# CONNECTORS_SELECTORS.net
KiCad netlist of a schematic drawn in Altium Designer
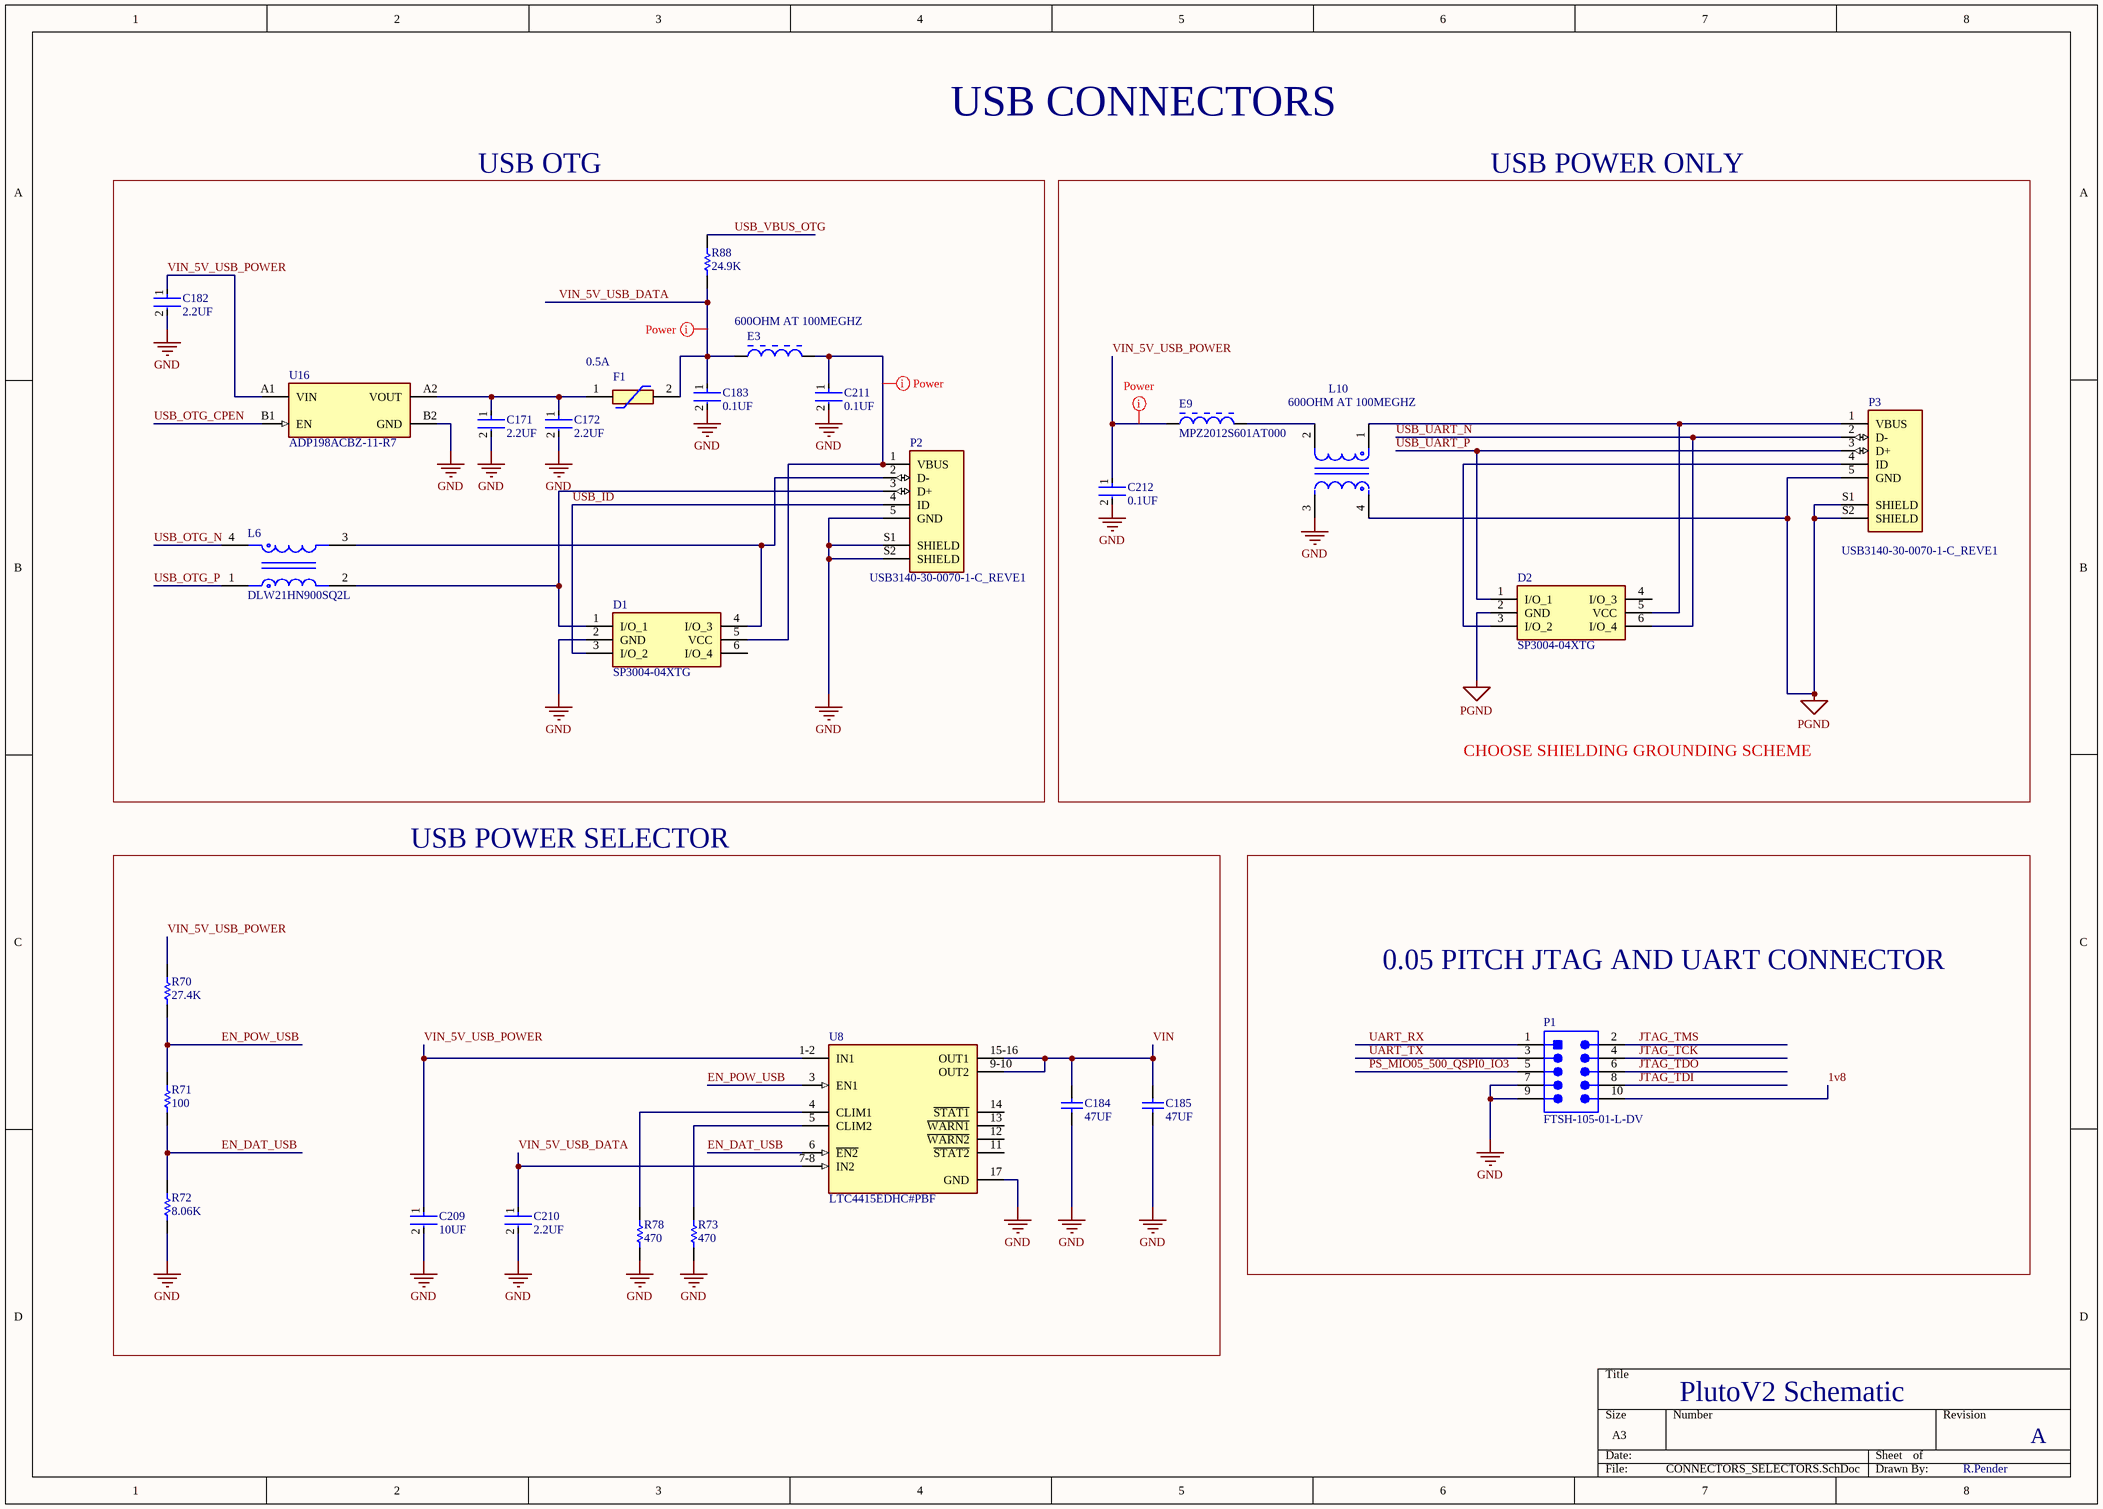
[diagram p0: CONNECTORS_SELECTORS.SchDoc]

(export (version "E")
  (design (tool "Eeschema 10.0.6"))
  (components
    (comp (ref "C171")
      (value "2.2UF")
      (footprint "FP-GRM188-0_2-IPC_C")
      (description "Chip Multilayer Ceramic Capacitors for General Purpose, 0603, 2.2uF, X5R, 15%, 10%, 50V")
      (fields (field (name "TOLERANCE") "10%"))
      (libsource (lib "Altium Content Vault") (part "11868f565c42a9108669ba33697ecf6"))
    )
    (comp (ref "C172")
      (value "2.2UF")
      (footprint "FP-GRM188-0_2-IPC_C")
      (description "Chip Multilayer Ceramic Capacitors for General Purpose, 0603, 2.2uF, X5R, 15%, 10%, 50V")
      (fields (field (name "TOLERANCE") "10%"))
      (libsource (lib "Altium Content Vault") (part "11868f565c42a9108669ba33697ecf6"))
    )
    (comp (ref "C182")
      (value "2.2UF")
      (footprint "FP-GRM188-0_2-IPC_C")
      (description "Chip Multilayer Ceramic Capacitors for General Purpose, 0603, 2.2uF, X5R, 15%, 10%, 50V")
      (fields (field (name "TOLERANCE") "10%"))
      (libsource (lib "Altium Content Vault") (part "11868f565c42a9108669ba33697ecf6"))
    )
    (comp (ref "C183")
      (value "0.1UF")
      (footprint "FP-CL10-IPC_A")
      (description "Cap Ceramic 100nF 100V X7R ±10% Pad SMD 0603 +125°C T/R")
      (fields (field (name "TOLERANCE") "10%"))
      (libsource (lib "Altium Content Vault") (part "b4654b650e69147ec39a6b967a45e02"))
    )
    (comp (ref "C184")
      (value "47UF")
      (footprint "TAYO-JMK212BBJ476MG-T_L")
      (fields
        (field (name "MANUFACTURER") "Taiyo Yuden")
        (field (name "TOLERANCE") "±20%")
        (field (name "PCN PART NUMBER") "X5R,X7RDielectrics23/Jan/2008")
      )
      (libsource (lib "Altium Content Vault") (part "CAP-NP-2"))
    )
    (comp (ref "C185")
      (value "47UF")
      (footprint "TAYO-JMK212BBJ476MG-T_L")
      (fields
        (field (name "MANUFACTURER") "Taiyo Yuden")
        (field (name "TOLERANCE") "±20%")
        (field (name "PCN PART NUMBER") "X5R,X7RDielectrics23/Jan/2008")
      )
      (libsource (lib "Altium Content Vault") (part "CAP-NP-2"))
    )
    (comp (ref "C209")
      (value "10UF")
      (footprint "FP-GRM188-0_15-MFG")
      (description "Chip Multilayer Ceramic Capacitors for General Purpose, 0603, 10uF, X5R, 15%, 20%, 10V")
      (fields (field (name "TOLERANCE") "20%"))
      (libsource (lib "Altium Content Vault") (part "02cd4be3c70576c341d710602a673aa"))
    )
    (comp (ref "C210")
      (value "2.2UF")
      (footprint "FP-GRM188-0_2-IPC_C")
      (description "Chip Multilayer Ceramic Capacitors for General Purpose, 0603, 2.2uF, X5R, 15%, 10%, 50V")
      (fields (field (name "TOLERANCE") "10%"))
      (libsource (lib "Altium Content Vault") (part "11868f565c42a9108669ba33697ecf6"))
    )
    (comp (ref "C211")
      (value "0.1UF")
      (footprint "FP-CL10-IPC_A")
      (description "Cap Ceramic 100nF 100V X7R ±10% Pad SMD 0603 +125°C T/R")
      (fields (field (name "TOLERANCE") "10%"))
      (libsource (lib "Altium Content Vault") (part "b4654b650e69147ec39a6b967a45e02"))
    )
    (comp (ref "C212")
      (value "0.1UF")
      (footprint "FP-CL10-IPC_A")
      (description "Cap Ceramic 100nF 100V X7R ±10% Pad SMD 0603 +125°C T/R")
      (fields (field (name "TOLERANCE") "10%"))
      (libsource (lib "Altium Content Vault") (part "b4654b650e69147ec39a6b967a45e02"))
    )
    (comp (ref "D1")
      (value "SP3004-04XTG")
      (footprint "SamacSys:SOTFL50P160X60-6N")
      (description "TVS Diode (Uni-directional)")
      (libsource (lib "SamacSys") (part "SP3004-04XTG"))
    )
    (comp (ref "D2")
      (value "SP3004-04XTG")
      (footprint "SamacSys:SOTFL50P160X60-6N")
      (description "TVS Diode (Uni-directional)")
      (libsource (lib "SamacSys") (part "SP3004-04XTG"))
    )
    (comp (ref "E3")
      (value "600OHM AT 100MEGHZ")
      (footprint "TDK-MPZ2012_V")
      (description "Chip Bead, 0.1 Ohm, 2 A, -55 to 125 degC, 2-Pin SMD (0805), RoHS, Tape and Reel")
      (fields (field (name "PCN PART NUMBER") "MMZ,MPSSeriesOct/2014") (field (name "MANUFACTURER") "TDK"))
      (libsource (lib "Altium Content Vault") (part "BEAD-2"))
    )
    (comp (ref "E9")
      (value "MPZ2012S601AT000")
      (footprint "TDK-MPZ2012_V")
      (description "Chip Bead, 0.1 Ohm, 2 A, -55 to 125 degC, 2-Pin SMD (0805), RoHS, Tape and Reel")
      (fields (field (name "PCN PART NUMBER") "MMZ,MPSSeriesOct/2014") (field (name "MANUFACTURER") "TDK"))
      (libsource (lib "Altium Content Vault") (part "BEAD-2"))
    )
    (comp (ref "F1")
      (value "0.5A")
      (footprint "SamacSys:0402L010SLKR")
      (description "Resettable Fuse")
      (fields (field (name "MANUFACTURER_PART_NUMBER") "0402L050SLKR"))
      (libsource (lib "SamacSys") (part "0402L050SLKR"))
    )
    (comp (ref "L6")
      (value "DLW21HN900SQ2L")
      (footprint "FP-DLW21HN-MFG")
      (description "CMC 330MA 2LN 90 OHM SMD")
      (fields (field (name "TOLERANCE") "25%"))
      (libsource (lib "Altium Content Vault") (part "0a69a9865a8fa8fb197e9315ef85d0a"))
    )
    (comp (ref "L10")
      (value "600OHM AT 100MEGHZ")
      (footprint "FP-DLW5BS-MFG")
      (description "Common Mode Choke, 2020, 800Ω @ 100MHz, 0.056Ω, 40%, 2A")
      (fields (field (name "TOLERANCE") "40%"))
      (libsource (lib "Altium Content Vault") (part "7e18bf8fdb9f2485ca2bcdf9073d69f"))
    )
    (comp (ref "P1")
      (value "FTSH-105-01-L-DV")
      (footprint "SMTC-FTSH-105-01-L-DV_V")
      (description "Male Header, Pitch 1.27 mm, 2 x 5 Position, Height 5.96 mm, -55 to 125 degC, RoHS, Bulk")
      (fields (field (name "MANUFACTURER") "Samtec"))
      (libsource (lib "Altium Content Vault") (part "CN-2P-M-R10"))
    )
    (comp (ref "P2")
      (value "USB3140-30-0070-1-C_REVE1")
      (footprint "GCT_USB3140-30-0070-1-C_REVE1")
      (fields (field (name "MF") "Global Connector Technology") (field (name "MP") "USB3140-30-0070-1-C"))
      (libsource (lib "USB3140-30-0070-1-C_REVE1") (part "USB3140-30-0070-1-C_REVE1"))
    )
    (comp (ref "P3")
      (value "USB3140-30-0070-1-C_REVE1")
      (footprint "GCT_USB3140-30-0070-1-C_REVE1")
      (fields (field (name "MF") "Global Connector Technology") (field (name "MP") "USB3140-30-0070-1-C"))
      (libsource (lib "USB3140-30-0070-1-C_REVE1") (part "USB3140-30-0070-1-C_REVE1"))
    )
    (comp (ref "R70")
      (value "27.4K")
      (footprint "2-0402")
      (fields (field (name "PUBLISHER") "Altium Limited"))
      (libsource (lib "Panasonic Resistor") (part "ERJ2RK"))
    )
    (comp (ref "R71")
      (value "100")
      (footprint "2-0402")
      (fields (field (name "PUBLISHER") "Altium Limited"))
      (libsource (lib "Panasonic Resistor") (part "ERJ2RK"))
    )
    (comp (ref "R72")
      (value "8.06K")
      (footprint "2-0402")
      (fields (field (name "PUBLISHER") "Altium Limited"))
      (libsource (lib "Panasonic Resistor") (part "ERJ2RK"))
    )
    (comp (ref "R73")
      (value "470")
      (footprint "RESC1005X40X25ML05T10")
      (fields (field (name "PART NUMBER") "RC0402FR-07470RL") (field (name "MANUFACTURER") "Yageo / Phycomp"))
      (libsource (lib "Altium Content Vault") (part "RES"))
    )
    (comp (ref "R78")
      (value "470")
      (footprint "RESC1005X40X25ML05T10")
      (fields (field (name "PART NUMBER") "RC0402FR-07470RL") (field (name "MANUFACTURER") "Yageo / Phycomp"))
      (libsource (lib "Altium Content Vault") (part "RES"))
    )
    (comp (ref "R88")
      (value "24.9K")
      (footprint "2-0402")
      (fields (field (name "PUBLISHER") "Altium Limited"))
      (libsource (lib "Panasonic Resistor") (part "ERJ2RK"))
    )
    (comp (ref "U8")
      (value "LTC4415EDHC#PBF")
      (footprint "FP-DHC-16-05-08-1872-MFG")
      (description "IC OR CTRLR SRC SELECT 16DFN")
      (libsource (lib "Altium Content Vault") (part "3ca062e251a206593296efba02ab3fb"))
    )
    (comp (ref "U16")
      (value "ADP198ACBZ-11-R7")
      (footprint "FP-CB-4-4-MFG")
      (description "IC PWR SWITCH P-CHAN 1:1 4WLCSP")
      (libsource (lib "Altium Content Vault") (part "e79baadf0d63db38dbad7ddd3c26481"))
    )
  )
  (nets
    (net (code "1") (name "/1v8") (class "Default")
      (node (ref "P1") (pin "10") (pinfunction "10_10") (pintype "passive"))
    )
    (net (code "2") (name "/EN_DAT_USB") (class "Default")
      (node (ref "R71") (pin "2") (pinfunction "2_2") (pintype "passive"))
      (node (ref "R72") (pin "1") (pinfunction "1_1") (pintype "passive"))
      (node (ref "U8") (pin "6") (pinfunction "~{EN2}_6") (pintype "input"))
    )
    (net (code "3") (name "/EN_POW_USB") (class "Default")
      (node (ref "R70") (pin "2") (pinfunction "2_2") (pintype "passive"))
      (node (ref "R71") (pin "1") (pinfunction "1_1") (pintype "passive"))
      (node (ref "U8") (pin "3") (pinfunction "EN1_3") (pintype "input"))
    )
    (net (code "4") (name "/JTAG_TCK") (class "Default")
      (node (ref "P1") (pin "4") (pinfunction "4_4") (pintype "passive"))
    )
    (net (code "5") (name "/JTAG_TDI") (class "Default")
      (node (ref "P1") (pin "8") (pinfunction "8_8") (pintype "passive"))
    )
    (net (code "6") (name "/JTAG_TDO") (class "Default")
      (node (ref "P1") (pin "6") (pinfunction "6_6") (pintype "passive"))
    )
    (net (code "7") (name "/JTAG_TMS") (class "Default")
      (node (ref "P1") (pin "2") (pinfunction "2_2") (pintype "passive"))
    )
    (net (code "8") (name "/PS_MIO05_500_QSPI0_IO3") (class "Default")
      (node (ref "P1") (pin "5") (pinfunction "5_5") (pintype "passive"))
    )
    (net (code "9") (name "/UART_RX") (class "Default")
      (node (ref "P1") (pin "1") (pinfunction "1_1") (pintype "passive"))
    )
    (net (code "10") (name "/UART_TX") (class "Default")
      (node (ref "P1") (pin "3") (pinfunction "3_3") (pintype "passive"))
    )
    (net (code "11") (name "/USB_ID") (class "Default")
      (node (ref "D1") (pin "3") (pinfunction "I/O_2_3") (pintype "passive"))
      (node (ref "P2") (pin "4") (pinfunction "ID_4") (pintype "passive"))
    )
    (net (code "12") (name "/USB_OTG_CPEN") (class "Default")
      (node (ref "U16") (pin "B1") (pinfunction "EN_B1") (pintype "input"))
    )
    (net (code "13") (name "/USB_OTG_N") (class "Default")
      (node (ref "L6") (pin "4") (pinfunction "4_4") (pintype "passive"))
    )
    (net (code "14") (name "/USB_OTG_P") (class "Default")
      (node (ref "L6") (pin "1") (pinfunction "1_1") (pintype "passive"))
    )
    (net (code "15") (name "/USB_UART_N") (class "Default")
      (node (ref "D2") (pin "6") (pinfunction "I/O_4_6") (pintype "passive"))
      (node (ref "P3") (pin "2") (pinfunction "D-_2") (pintype "bidirectional"))
    )
    (net (code "16") (name "/USB_UART_P") (class "Default")
      (node (ref "D2") (pin "1") (pinfunction "I/O_1_1") (pintype "passive"))
      (node (ref "P3") (pin "3") (pinfunction "D+_3") (pintype "bidirectional"))
    )
    (net (code "17") (name "/USB_VBUS_OTG") (class "Default")
      (node (ref "R88") (pin "2") (pinfunction "2_2") (pintype "passive"))
    )
    (net (code "18") (name "/VIN") (class "Default")
      (node (ref "C184") (pin "1") (pinfunction "1_1") (pintype "passive"))
      (node (ref "C185") (pin "1") (pinfunction "1_1") (pintype "passive"))
      (node (ref "U8") (pin "15-16") (pinfunction "OUT1_15-16") (pintype "passive"))
      (node (ref "U8") (pin "9-10") (pinfunction "OUT2_9-10") (pintype "passive"))
    )
    (net (code "19") (name "/VIN_5V_USB_DATA") (class "Default")
      (node (ref "C183") (pin "1") (pinfunction "1_1") (pintype "passive"))
      (node (ref "C210") (pin "1") (pinfunction "1_1") (pintype "passive"))
      (node (ref "E3") (pin "1") (pinfunction "1_1") (pintype "passive"))
      (node (ref "F1") (pin "2") (pinfunction "2_2") (pintype "passive"))
      (node (ref "R88") (pin "1") (pinfunction "1_1") (pintype "passive"))
      (node (ref "U8") (pin "7-8") (pinfunction "IN2_7-8") (pintype "input"))
    )
    (net (code "20") (name "/VIN_5V_USB_POWER") (class "Default")
      (node (ref "C182") (pin "1") (pinfunction "1_1") (pintype "passive"))
      (node (ref "C209") (pin "1") (pinfunction "1_1") (pintype "passive"))
      (node (ref "C212") (pin "1") (pinfunction "1_1") (pintype "passive"))
      (node (ref "E9") (pin "1") (pinfunction "1_1") (pintype "passive"))
      (node (ref "R70") (pin "1") (pinfunction "1_1") (pintype "passive"))
      (node (ref "U16") (pin "A1") (pinfunction "VIN_A1") (pintype "power_in"))
      (node (ref "U8") (pin "1-2") (pinfunction "IN1_1-2") (pintype "power_in"))
    )
    (net (code "21") (name "GND") (class "Default")
      (node (ref "C171") (pin "2") (pinfunction "2_2") (pintype "passive"))
      (node (ref "C172") (pin "2") (pinfunction "2_2") (pintype "passive"))
      (node (ref "C182") (pin "2") (pinfunction "2_2") (pintype "passive"))
      (node (ref "C183") (pin "2") (pinfunction "2_2") (pintype "passive"))
      (node (ref "C184") (pin "2") (pinfunction "2_2") (pintype "passive"))
      (node (ref "C185") (pin "2") (pinfunction "2_2") (pintype "passive"))
      (node (ref "C209") (pin "2") (pinfunction "2_2") (pintype "passive"))
      (node (ref "C210") (pin "2") (pinfunction "2_2") (pintype "passive"))
      (node (ref "C211") (pin "2") (pinfunction "2_2") (pintype "passive"))
      (node (ref "C212") (pin "2") (pinfunction "2_2") (pintype "passive"))
      (node (ref "D1") (pin "2") (pinfunction "GND_2") (pintype "passive"))
      (node (ref "L10") (pin "3") (pinfunction "3_3") (pintype "passive"))
      (node (ref "P1") (pin "7") (pinfunction "7_7") (pintype "passive"))
      (node (ref "P1") (pin "9") (pinfunction "9_9") (pintype "passive"))
      (node (ref "P2") (pin "5") (pinfunction "GND_5") (pintype "power_in"))
      (node (ref "P2") (pin "S1") (pinfunction "SHIELD_S1") (pintype "passive"))
      (node (ref "P2") (pin "S2") (pinfunction "SHIELD_S2") (pintype "passive"))
      (node (ref "R72") (pin "2") (pinfunction "2_2") (pintype "passive"))
      (node (ref "R73") (pin "2") (pinfunction "2_2") (pintype "passive"))
      (node (ref "R78") (pin "2") (pinfunction "2_2") (pintype "passive"))
      (node (ref "U16") (pin "B2") (pinfunction "GND_B2") (pintype "power_in"))
      (node (ref "U8") (pin "17") (pinfunction "GND_17") (pintype "power_in"))
    )
    (net (code "22") (name "Net-(D1-I{slash}O_1)") (class "Default")
      (node (ref "D1") (pin "1") (pinfunction "I/O_1_1") (pintype "passive"))
      (node (ref "L6") (pin "2") (pinfunction "2_2") (pintype "passive"))
      (node (ref "P2") (pin "3") (pinfunction "D+_3") (pintype "bidirectional"))
    )
    (net (code "23") (name "Net-(D1-I{slash}O_3)") (class "Default")
      (node (ref "D1") (pin "4") (pinfunction "I/O_3_4") (pintype "passive"))
      (node (ref "L6") (pin "3") (pinfunction "3_3") (pintype "passive"))
      (node (ref "P2") (pin "2") (pinfunction "D-_2") (pintype "bidirectional"))
    )
    (net (code "24") (name "Net-(D1-VCC)") (class "Default")
      (node (ref "C211") (pin "1") (pinfunction "1_1") (pintype "passive"))
      (node (ref "D1") (pin "5") (pinfunction "VCC_5") (pintype "passive"))
      (node (ref "E3") (pin "2") (pinfunction "2_2") (pintype "passive"))
      (node (ref "P2") (pin "1") (pinfunction "VBUS_1") (pintype "power_in"))
    )
    (net (code "25") (name "Net-(D2-I{slash}O_2)") (class "Default")
      (node (ref "D2") (pin "3") (pinfunction "I/O_2_3") (pintype "passive"))
      (node (ref "P3") (pin "4") (pinfunction "ID_4") (pintype "passive"))
    )
    (net (code "26") (name "Net-(D2-VCC)") (class "Default")
      (node (ref "D2") (pin "5") (pinfunction "VCC_5") (pintype "passive"))
      (node (ref "L10") (pin "1") (pinfunction "1_1") (pintype "passive"))
      (node (ref "P3") (pin "1") (pinfunction "VBUS_1") (pintype "power_in"))
    )
    (net (code "27") (name "Net-(E9-Pad2)") (class "Default")
      (node (ref "E9") (pin "2") (pinfunction "2_2") (pintype "passive"))
      (node (ref "L10") (pin "2") (pinfunction "2_2") (pintype "passive"))
    )
    (net (code "28") (name "Net-(U8-CLIM1)") (class "Default")
      (node (ref "R78") (pin "1") (pinfunction "1_1") (pintype "passive"))
      (node (ref "U8") (pin "4") (pinfunction "CLIM1_4") (pintype "passive"))
    )
    (net (code "29") (name "Net-(U8-CLIM2)") (class "Default")
      (node (ref "R73") (pin "1") (pinfunction "1_1") (pintype "passive"))
      (node (ref "U8") (pin "5") (pinfunction "CLIM2_5") (pintype "passive"))
    )
    (net (code "30") (name "Net-(U16-VOUT)") (class "Default")
      (node (ref "C171") (pin "1") (pinfunction "1_1") (pintype "passive"))
      (node (ref "C172") (pin "1") (pinfunction "1_1") (pintype "passive"))
      (node (ref "F1") (pin "1") (pinfunction "1_1") (pintype "passive"))
      (node (ref "U16") (pin "A2") (pinfunction "VOUT_A2") (pintype "passive"))
    )
    (net (code "31") (name "PGND") (class "Default")
      (node (ref "D2") (pin "2") (pinfunction "GND_2") (pintype "passive"))
      (node (ref "L10") (pin "4") (pinfunction "4_4") (pintype "passive"))
      (node (ref "P3") (pin "5") (pinfunction "GND_5") (pintype "power_in"))
      (node (ref "P3") (pin "S1") (pinfunction "SHIELD_S1") (pintype "passive"))
      (node (ref "P3") (pin "S2") (pinfunction "SHIELD_S2") (pintype "passive"))
    )
    (net (code "32") (name "unconnected-(D1-I{slash}O_4-Pad6)") (class "Default")
      (node (ref "D1") (pin "6") (pinfunction "I/O_4_6") (pintype "passive"))
    )
    (net (code "33") (name "unconnected-(D2-I{slash}O_3-Pad4)") (class "Default")
      (node (ref "D2") (pin "4") (pinfunction "I/O_3_4") (pintype "passive"))
    )
    (net (code "34") (name "unconnected-(U8-~{STAT1}-Pad14)") (class "Default")
      (node (ref "U8") (pin "14") (pinfunction "~{STAT1}_14") (pintype "open_collector"))
    )
    (net (code "35") (name "unconnected-(U8-~{STAT2}-Pad11)") (class "Default")
      (node (ref "U8") (pin "11") (pinfunction "~{STAT2}_11") (pintype "open_collector"))
    )
    (net (code "36") (name "unconnected-(U8-~{WARN1}-Pad13)") (class "Default")
      (node (ref "U8") (pin "13") (pinfunction "~{WARN1}_13") (pintype "passive"))
    )
    (net (code "37") (name "unconnected-(U8-~{WARN2}-Pad12)") (class "Default")
      (node (ref "U8") (pin "12") (pinfunction "~{WARN2}_12") (pintype "passive"))
    )
  )
)
